# picdiv.net
KiCad netlist of a schematic drawn in EAGLE
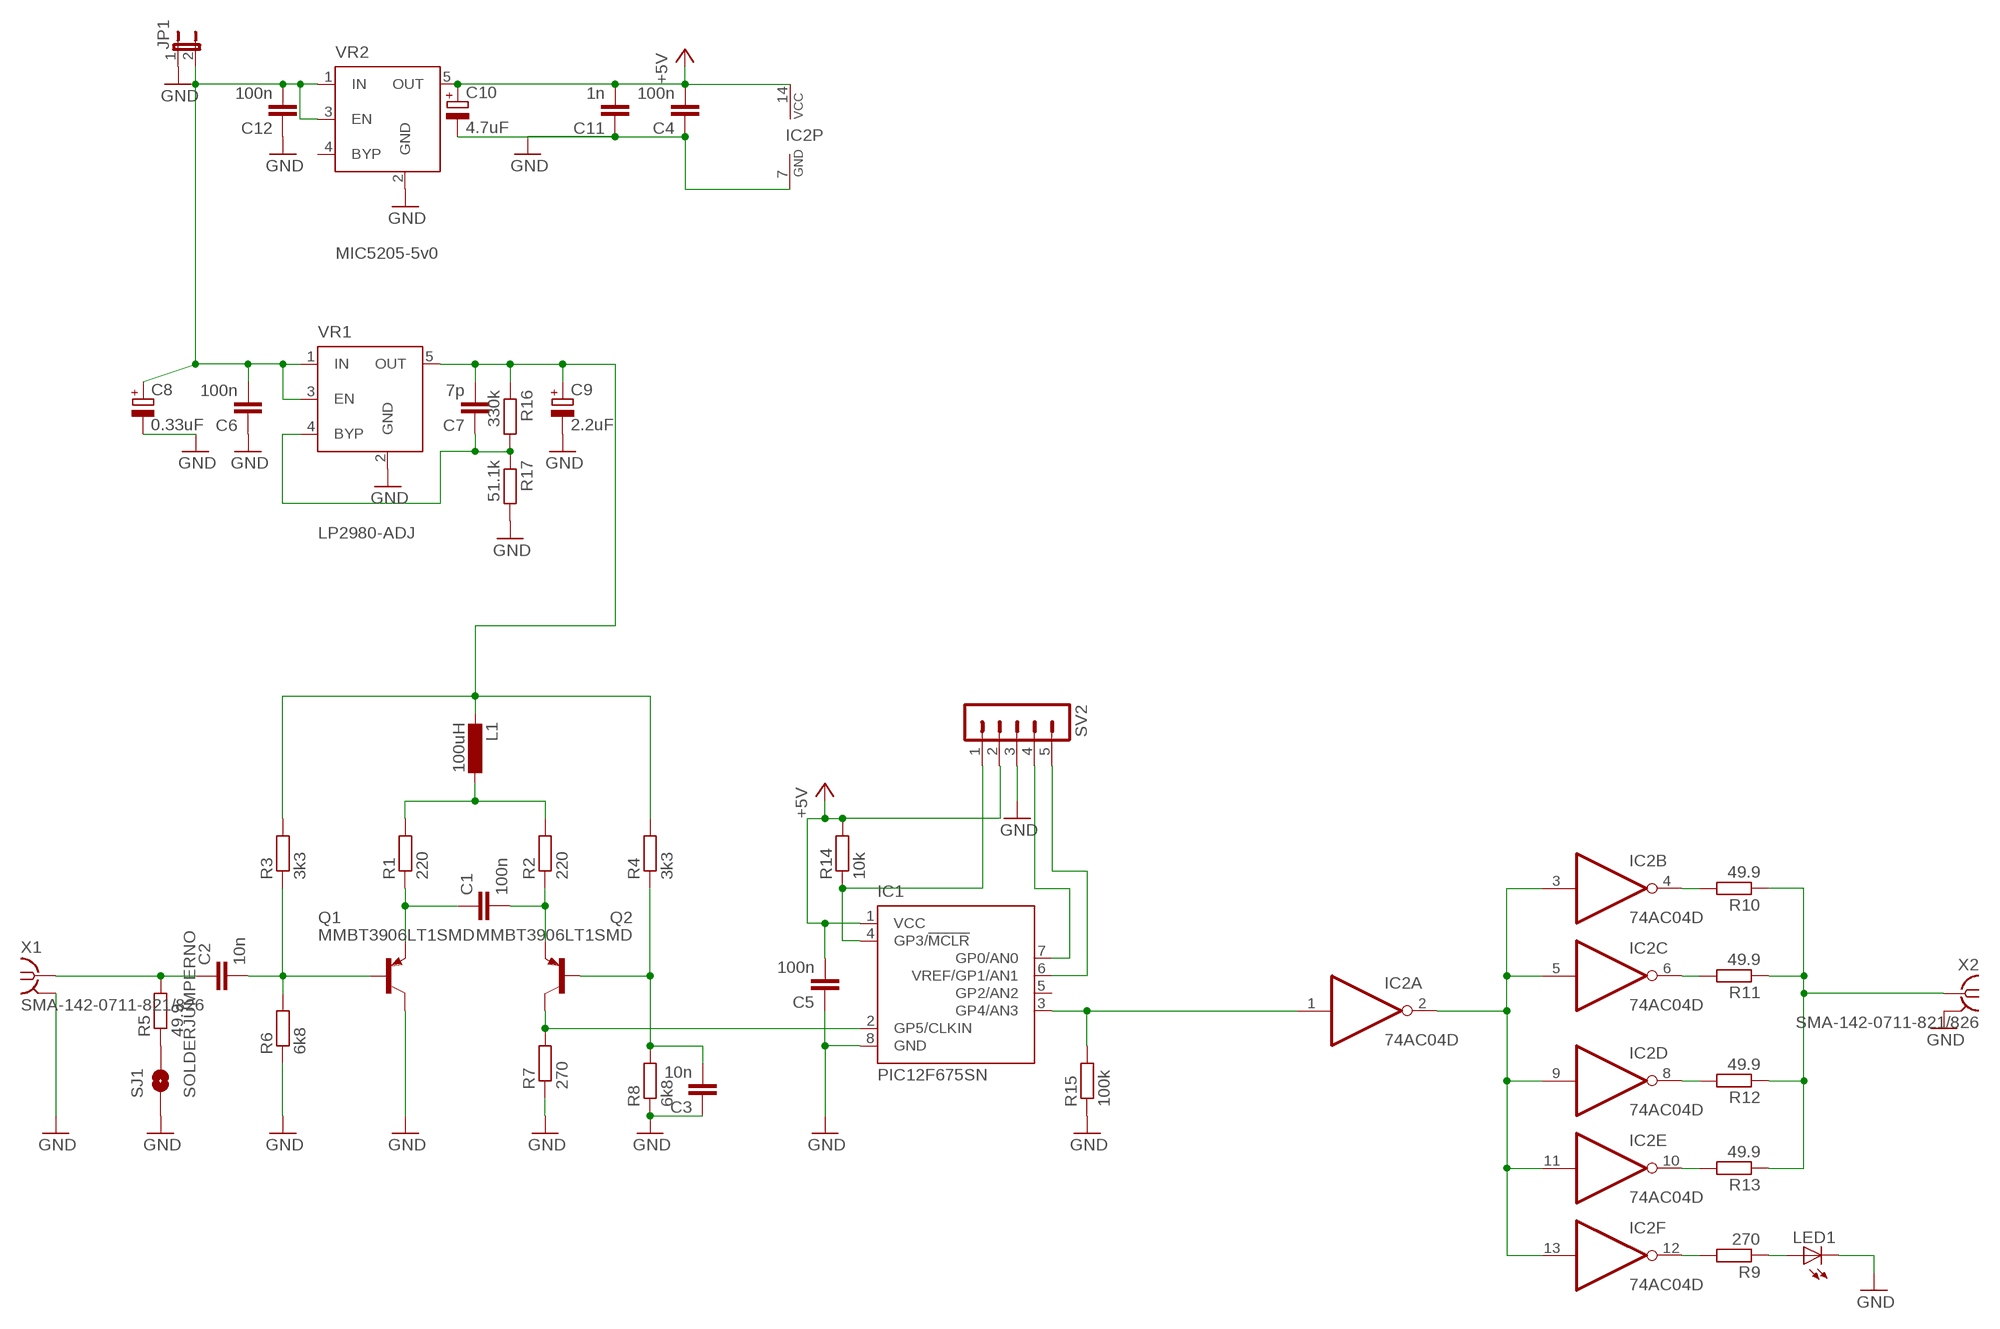
[diagram p0: schematic, sheet 1]

(export (version "E")
  (design (tool "Eeschema 10.0.6"))
  (components
    (comp (ref "C1")
      (value "100n")
      (footprint "eagle-import:C0603")
      (libsource (lib "eagle-import") (part "C-EUC0603"))
    )
    (comp (ref "C2")
      (value "10n")
      (footprint "eagle-import:C0603")
      (libsource (lib "eagle-import") (part "C-EUC0603"))
    )
    (comp (ref "C3")
      (value "10n")
      (footprint "eagle-import:C0603")
      (libsource (lib "eagle-import") (part "C-EUC0603"))
    )
    (comp (ref "C4")
      (value "100n")
      (footprint "eagle-import:C0603")
      (libsource (lib "eagle-import") (part "C-EUC0603"))
    )
    (comp (ref "C5")
      (value "100n")
      (footprint "eagle-import:C0603")
      (libsource (lib "eagle-import") (part "C-EUC0603"))
    )
    (comp (ref "C6")
      (value "100n")
      (footprint "eagle-import:C0603")
      (libsource (lib "eagle-import") (part "C-EUC0603"))
    )
    (comp (ref "C7")
      (value "7p")
      (footprint "eagle-import:C0603")
      (libsource (lib "eagle-import") (part "C-EUC0603"))
    )
    (comp (ref "C8")
      (value "0.33uF")
      (footprint "eagle-import:SMC_A")
      (libsource (lib "eagle-import") (part "CPOL-EUSMCA"))
    )
    (comp (ref "C9")
      (value "2.2uF")
      (footprint "eagle-import:SMC_A")
      (libsource (lib "eagle-import") (part "CPOL-EUSMCA"))
    )
    (comp (ref "C10")
      (value "4.7uF")
      (footprint "eagle-import:SMC_A")
      (libsource (lib "eagle-import") (part "CPOL-EUSMCA"))
    )
    (comp (ref "C11")
      (value "1n")
      (footprint "eagle-import:C0603")
      (libsource (lib "eagle-import") (part "C-EUC0603"))
    )
    (comp (ref "C12")
      (value "100n")
      (footprint "eagle-import:C0603")
      (libsource (lib "eagle-import") (part "C-EUC0603"))
    )
    (comp (ref "IC1")
      (value "PIC12F675SN")
      (footprint "eagle-import:SO-08")
      (fields (field (name "MF") "MICROCHIP") (field (name "MPN") "PIC12F675-E/SN"))
      (libsource (lib "eagle-import") (part "PIC12F675SN"))
    )
    (comp (ref "IC2")
      (value "74AC04D")
      (footprint "eagle-import:SO14")
      (libsource (lib "eagle-import") (part "7404DAC"))
    )
    (comp (ref "JP1")
      (value "JUMPER-2PTH")
      (footprint "eagle-import:1X02")
      (libsource (lib "eagle-import") (part "JUMPER-2PTH"))
    )
    (comp (ref "L1")
      (value "100uH")
      (footprint "eagle-import:L2012C")
      (libsource (lib "eagle-import") (part "L-EUL2012C"))
    )
    (comp (ref "LED1")
      (value "LEDCHIPLED_0603")
      (footprint "eagle-import:CHIPLED_0603")
      (libsource (lib "eagle-import") (part "LEDCHIPLED_0603"))
    )
    (comp (ref "Q1")
      (value "MMBT3906LT1SMD")
      (footprint "eagle-import:SOT23-BEC")
      (libsource (lib "eagle-import") (part "MMBT3906SMDLT1"))
    )
    (comp (ref "Q2")
      (value "MMBT3906LT1SMD")
      (footprint "eagle-import:SOT23-BEC")
      (libsource (lib "eagle-import") (part "MMBT3906SMDLT1"))
    )
    (comp (ref "R1")
      (value "220")
      (footprint "eagle-import:R0603")
      (libsource (lib "eagle-import") (part "R-EU_R0603"))
    )
    (comp (ref "R2")
      (value "220")
      (footprint "eagle-import:R0603")
      (libsource (lib "eagle-import") (part "R-EU_R0603"))
    )
    (comp (ref "R3")
      (value "3k3")
      (footprint "eagle-import:R0603")
      (libsource (lib "eagle-import") (part "R-EU_R0603"))
    )
    (comp (ref "R4")
      (value "3k3")
      (footprint "eagle-import:R0603")
      (libsource (lib "eagle-import") (part "R-EU_R0603"))
    )
    (comp (ref "R5")
      (value "49.9")
      (footprint "eagle-import:R0603")
      (libsource (lib "eagle-import") (part "R-EU_R0603"))
    )
    (comp (ref "R6")
      (value "6k8")
      (footprint "eagle-import:R0603")
      (libsource (lib "eagle-import") (part "R-EU_R0603"))
    )
    (comp (ref "R7")
      (value "270")
      (footprint "eagle-import:R0603")
      (libsource (lib "eagle-import") (part "R-EU_R0603"))
    )
    (comp (ref "R8")
      (value "6k8")
      (footprint "eagle-import:R0603")
      (libsource (lib "eagle-import") (part "R-EU_R0603"))
    )
    (comp (ref "R9")
      (value "270")
      (footprint "eagle-import:R0603")
      (libsource (lib "eagle-import") (part "R-EU_R0603"))
    )
    (comp (ref "R10")
      (value "49.9")
      (footprint "eagle-import:R0603")
      (libsource (lib "eagle-import") (part "R-EU_R0603"))
    )
    (comp (ref "R11")
      (value "49.9")
      (footprint "eagle-import:R0603")
      (libsource (lib "eagle-import") (part "R-EU_R0603"))
    )
    (comp (ref "R12")
      (value "49.9")
      (footprint "eagle-import:R0603")
      (libsource (lib "eagle-import") (part "R-EU_R0603"))
    )
    (comp (ref "R13")
      (value "49.9")
      (footprint "eagle-import:R0603")
      (libsource (lib "eagle-import") (part "R-EU_R0603"))
    )
    (comp (ref "R14")
      (value "10k")
      (footprint "eagle-import:R0603")
      (libsource (lib "eagle-import") (part "R-EU_R0603"))
    )
    (comp (ref "R15")
      (value "100k")
      (footprint "eagle-import:R0603")
      (libsource (lib "eagle-import") (part "R-EU_R0603"))
    )
    (comp (ref "R16")
      (value "330k")
      (footprint "eagle-import:R0603")
      (libsource (lib "eagle-import") (part "R-EU_R0603"))
    )
    (comp (ref "R17")
      (value "51.1k")
      (footprint "eagle-import:R0603")
      (libsource (lib "eagle-import") (part "R-EU_R0603"))
    )
    (comp (ref "SJ1")
      (value "SOLDERJUMPERNO")
      (footprint "eagle-import:SJ_2S-NO")
      (libsource (lib "eagle-import") (part "SOLDERJUMPERNO"))
    )
    (comp (ref "SV2")
      (value "MA05-1")
      (footprint "eagle-import:MA05-1")
      (libsource (lib "eagle-import") (part "MA05-1"))
    )
    (comp (ref "VR1")
      (value "LP2980-ADJ")
      (footprint "eagle-import:SOT23-5")
      (libsource (lib "eagle-import") (part "MIC5219XX"))
    )
    (comp (ref "VR2")
      (value "MIC5205-5v0")
      (footprint "eagle-import:SOT23-5")
      (libsource (lib "eagle-import") (part "MIC5219XX"))
    )
    (comp (ref "X1")
      (value "SMA-142-0711-821/826")
      (footprint "eagle-import:J502-ND-142-0711-821_826")
      (fields (field (name "MF") "JOHNSON COMPONENTS") (field (name "MPN") "142-0711-821"))
      (libsource (lib "eagle-import") (part "SMA-142-0711-821/826"))
    )
    (comp (ref "X2")
      (value "SMA-142-0711-821/826")
      (footprint "eagle-import:J502-ND-142-0711-821_826")
      (fields (field (name "MF") "JOHNSON COMPONENTS") (field (name "MPN") "142-0711-821"))
      (libsource (lib "eagle-import") (part "SMA-142-0711-821/826"))
    )
  )
  (nets
    (net (code "1") (name "+5V") (class "Default")
      (node (ref "C10") (pin "+") (pinfunction "+_+") (pintype "passive"))
      (node (ref "C11") (pin "2") (pinfunction "2_2") (pintype "passive"))
      (node (ref "C4") (pin "2") (pinfunction "2_2") (pintype "passive"))
      (node (ref "C5") (pin "2") (pinfunction "2_2") (pintype "passive"))
      (node (ref "IC1") (pin "1") (pinfunction "VCC_1") (pintype "power_in"))
      (node (ref "IC2") (pin "14") (pinfunction "VCC_14") (pintype "power_in"))
      (node (ref "R14") (pin "2") (pinfunction "2_2") (pintype "passive"))
      (node (ref "SV2") (pin "2") (pinfunction "2_2") (pintype "passive"))
      (node (ref "VR2") (pin "5") (pinfunction "OUT_5") (pintype "output"))
    )
    (net (code "2") (name "GND") (class "Default")
      (node (ref "C10") (pin "-") (pinfunction "-_-") (pintype "passive"))
      (node (ref "C11") (pin "1") (pinfunction "1_1") (pintype "passive"))
      (node (ref "C12") (pin "1") (pinfunction "1_1") (pintype "passive"))
      (node (ref "C3") (pin "1") (pinfunction "1_1") (pintype "passive"))
      (node (ref "C4") (pin "1") (pinfunction "1_1") (pintype "passive"))
      (node (ref "C5") (pin "1") (pinfunction "1_1") (pintype "passive"))
      (node (ref "C6") (pin "1") (pinfunction "1_1") (pintype "passive"))
      (node (ref "C8") (pin "-") (pinfunction "-_-") (pintype "passive"))
      (node (ref "C9") (pin "-") (pinfunction "-_-") (pintype "passive"))
      (node (ref "IC1") (pin "8") (pinfunction "GND_8") (pintype "power_in"))
      (node (ref "IC2") (pin "7") (pinfunction "GND_7") (pintype "power_in"))
      (node (ref "JP1") (pin "1") (pinfunction "1_1") (pintype "passive"))
      (node (ref "LED1") (pin "C") (pinfunction "C_C") (pintype "passive"))
      (node (ref "Q1") (pin "C") (pinfunction "C_C") (pintype "passive"))
      (node (ref "R15") (pin "1") (pinfunction "1_1") (pintype "passive"))
      (node (ref "R17") (pin "2") (pinfunction "2_2") (pintype "passive"))
      (node (ref "R6") (pin "1") (pinfunction "1_1") (pintype "passive"))
      (node (ref "R7") (pin "1") (pinfunction "1_1") (pintype "passive"))
      (node (ref "R8") (pin "1") (pinfunction "1_1") (pintype "passive"))
      (node (ref "SJ1") (pin "1") (pinfunction "1_1") (pintype "passive"))
      (node (ref "SV2") (pin "3") (pinfunction "3_3") (pintype "passive"))
      (node (ref "VR1") (pin "2") (pinfunction "GND_2") (pintype "power_in"))
      (node (ref "VR2") (pin "2") (pinfunction "GND_2") (pintype "power_in"))
      (node (ref "X1") (pin "G@1") (pinfunction "GND_G@1") (pintype "power_in"))
      (node (ref "X2") (pin "G@1") (pinfunction "GND_G@1") (pintype "power_in"))
    )
    (net (code "3") (name "Net-(C1-Pad1)") (class "Default")
      (node (ref "C1") (pin "1") (pinfunction "1_1") (pintype "passive"))
      (node (ref "Q1") (pin "E") (pinfunction "E_E") (pintype "passive"))
      (node (ref "R1") (pin "1") (pinfunction "1_1") (pintype "passive"))
    )
    (net (code "4") (name "Net-(C1-Pad2)") (class "Default")
      (node (ref "C1") (pin "2") (pinfunction "2_2") (pintype "passive"))
      (node (ref "Q2") (pin "E") (pinfunction "E_E") (pintype "passive"))
      (node (ref "R2") (pin "1") (pinfunction "1_1") (pintype "passive"))
    )
    (net (code "5") (name "Net-(C2-Pad1)") (class "Default")
      (node (ref "C2") (pin "1") (pinfunction "1_1") (pintype "passive"))
      (node (ref "R5") (pin "2") (pinfunction "2_2") (pintype "passive"))
      (node (ref "X1") (pin "1") (pinfunction "1_1") (pintype "passive"))
    )
    (net (code "6") (name "Net-(C2-Pad2)") (class "Default")
      (node (ref "C2") (pin "2") (pinfunction "2_2") (pintype "passive"))
      (node (ref "Q1") (pin "B") (pinfunction "B_B") (pintype "passive"))
      (node (ref "R3") (pin "1") (pinfunction "1_1") (pintype "passive"))
      (node (ref "R6") (pin "2") (pinfunction "2_2") (pintype "passive"))
    )
    (net (code "7") (name "Net-(C3-Pad2)") (class "Default")
      (node (ref "C3") (pin "2") (pinfunction "2_2") (pintype "passive"))
      (node (ref "Q2") (pin "B") (pinfunction "B_B") (pintype "passive"))
      (node (ref "R4") (pin "1") (pinfunction "1_1") (pintype "passive"))
      (node (ref "R8") (pin "2") (pinfunction "2_2") (pintype "passive"))
    )
    (net (code "8") (name "Net-(IC1-GP0{slash}AN0)") (class "Default")
      (node (ref "IC1") (pin "7") (pinfunction "GP0/AN0_7") (pintype "bidirectional"))
      (node (ref "SV2") (pin "4") (pinfunction "4_4") (pintype "passive"))
    )
    (net (code "9") (name "Net-(IC1-GP3{slash}~{MCLR})") (class "Default")
      (node (ref "IC1") (pin "4") (pinfunction "GP3/~{MCLR}_4") (pintype "input"))
      (node (ref "R14") (pin "1") (pinfunction "1_1") (pintype "passive"))
      (node (ref "SV2") (pin "1") (pinfunction "1_1") (pintype "passive"))
    )
    (net (code "10") (name "Net-(IC1-GP4{slash}AN3)") (class "Default")
      (node (ref "IC1") (pin "3") (pinfunction "GP4/AN3_3") (pintype "bidirectional"))
      (node (ref "IC2") (pin "1") (pinfunction "I_1") (pintype "input"))
      (node (ref "R15") (pin "2") (pinfunction "2_2") (pintype "passive"))
    )
    (net (code "11") (name "Net-(IC1-GP5{slash}CLKIN)") (class "Default")
      (node (ref "IC1") (pin "2") (pinfunction "GP5/CLKIN_2") (pintype "bidirectional"))
      (node (ref "Q2") (pin "C") (pinfunction "C_C") (pintype "passive"))
      (node (ref "R7") (pin "2") (pinfunction "2_2") (pintype "passive"))
    )
    (net (code "12") (name "Net-(IC1-VREF{slash}GP1{slash}AN1)") (class "Default")
      (node (ref "IC1") (pin "6") (pinfunction "VREF/GP1/AN1_6") (pintype "bidirectional"))
      (node (ref "SV2") (pin "5") (pinfunction "5_5") (pintype "passive"))
    )
    (net (code "13") (name "Net-(IC2A-O)") (class "Default")
      (node (ref "IC2") (pin "11") (pinfunction "I_11") (pintype "input"))
      (node (ref "IC2") (pin "13") (pinfunction "I_13") (pintype "input"))
      (node (ref "IC2") (pin "2") (pinfunction "O_2") (pintype "output"))
      (node (ref "IC2") (pin "3") (pinfunction "I_3") (pintype "input"))
      (node (ref "IC2") (pin "5") (pinfunction "I_5") (pintype "input"))
      (node (ref "IC2") (pin "9") (pinfunction "I_9") (pintype "input"))
    )
    (net (code "14") (name "Net-(IC2B-O)") (class "Default")
      (node (ref "IC2") (pin "4") (pinfunction "O_4") (pintype "output"))
      (node (ref "R10") (pin "2") (pinfunction "2_2") (pintype "passive"))
    )
    (net (code "15") (name "Net-(IC2C-O)") (class "Default")
      (node (ref "IC2") (pin "6") (pinfunction "O_6") (pintype "output"))
      (node (ref "R11") (pin "2") (pinfunction "2_2") (pintype "passive"))
    )
    (net (code "16") (name "Net-(IC2D-O)") (class "Default")
      (node (ref "IC2") (pin "8") (pinfunction "O_8") (pintype "output"))
      (node (ref "R12") (pin "2") (pinfunction "2_2") (pintype "passive"))
    )
    (net (code "17") (name "Net-(IC2E-O)") (class "Default")
      (node (ref "IC2") (pin "10") (pinfunction "O_10") (pintype "output"))
      (node (ref "R13") (pin "2") (pinfunction "2_2") (pintype "passive"))
    )
    (net (code "18") (name "Net-(IC2F-O)") (class "Default")
      (node (ref "IC2") (pin "12") (pinfunction "O_12") (pintype "output"))
      (node (ref "R9") (pin "2") (pinfunction "2_2") (pintype "passive"))
    )
    (net (code "19") (name "Net-(L1-Pad1)") (class "Default")
      (node (ref "L1") (pin "1") (pinfunction "1_1") (pintype "passive"))
      (node (ref "R1") (pin "2") (pinfunction "2_2") (pintype "passive"))
      (node (ref "R2") (pin "2") (pinfunction "2_2") (pintype "passive"))
    )
    (net (code "20") (name "Net-(LED1-PadA)") (class "Default")
      (node (ref "LED1") (pin "A") (pinfunction "A_A") (pintype "passive"))
      (node (ref "R9") (pin "1") (pinfunction "1_1") (pintype "passive"))
    )
    (net (code "21") (name "Net-(R5-Pad1)") (class "Default")
      (node (ref "R5") (pin "1") (pinfunction "1_1") (pintype "passive"))
      (node (ref "SJ1") (pin "2") (pinfunction "2_2") (pintype "passive"))
    )
    (net (code "22") (name "Net-(R10-Pad1)") (class "Default")
      (node (ref "R10") (pin "1") (pinfunction "1_1") (pintype "passive"))
      (node (ref "R11") (pin "1") (pinfunction "1_1") (pintype "passive"))
      (node (ref "R12") (pin "1") (pinfunction "1_1") (pintype "passive"))
      (node (ref "R13") (pin "1") (pinfunction "1_1") (pintype "passive"))
      (node (ref "X2") (pin "1") (pinfunction "1_1") (pintype "passive"))
    )
    (net (code "23") (name "Net-(VR1-BYP)") (class "Default")
      (node (ref "C7") (pin "1") (pinfunction "1_1") (pintype "passive"))
      (node (ref "R16") (pin "2") (pinfunction "2_2") (pintype "passive"))
      (node (ref "R17") (pin "1") (pinfunction "1_1") (pintype "passive"))
      (node (ref "VR1") (pin "4") (pinfunction "BYP_4") (pintype "passive"))
    )
    (net (code "24") (name "Net-(VR1-EN)") (class "Default")
      (node (ref "C12") (pin "2") (pinfunction "2_2") (pintype "passive"))
      (node (ref "C6") (pin "2") (pinfunction "2_2") (pintype "passive"))
      (node (ref "C8") (pin "+") (pinfunction "+_+") (pintype "passive"))
      (node (ref "JP1") (pin "2") (pinfunction "2_2") (pintype "passive"))
      (node (ref "VR1") (pin "1") (pinfunction "IN_1") (pintype "input"))
      (node (ref "VR1") (pin "3") (pinfunction "EN_3") (pintype "input"))
      (node (ref "VR2") (pin "1") (pinfunction "IN_1") (pintype "input"))
      (node (ref "VR2") (pin "3") (pinfunction "EN_3") (pintype "input"))
    )
    (net (code "25") (name "Net-(VR1-OUT)") (class "Default")
      (node (ref "C7") (pin "2") (pinfunction "2_2") (pintype "passive"))
      (node (ref "C9") (pin "+") (pinfunction "+_+") (pintype "passive"))
      (node (ref "L1") (pin "2") (pinfunction "2_2") (pintype "passive"))
      (node (ref "R16") (pin "1") (pinfunction "1_1") (pintype "passive"))
      (node (ref "R3") (pin "2") (pinfunction "2_2") (pintype "passive"))
      (node (ref "R4") (pin "2") (pinfunction "2_2") (pintype "passive"))
      (node (ref "VR1") (pin "5") (pinfunction "OUT_5") (pintype "output"))
    )
    (net (code "26") (name "unconnected-(IC1-GP2{slash}AN2-Pad5)") (class "Default")
      (node (ref "IC1") (pin "5") (pinfunction "GP2/AN2_5") (pintype "bidirectional"))
    )
    (net (code "27") (name "unconnected-(VR2-BYP-Pad4)") (class "Default")
      (node (ref "VR2") (pin "4") (pinfunction "BYP_4") (pintype "passive"))
    )
  )
)
